# system_controller.net
KiCad netlist of a schematic drawn in Altium Designer
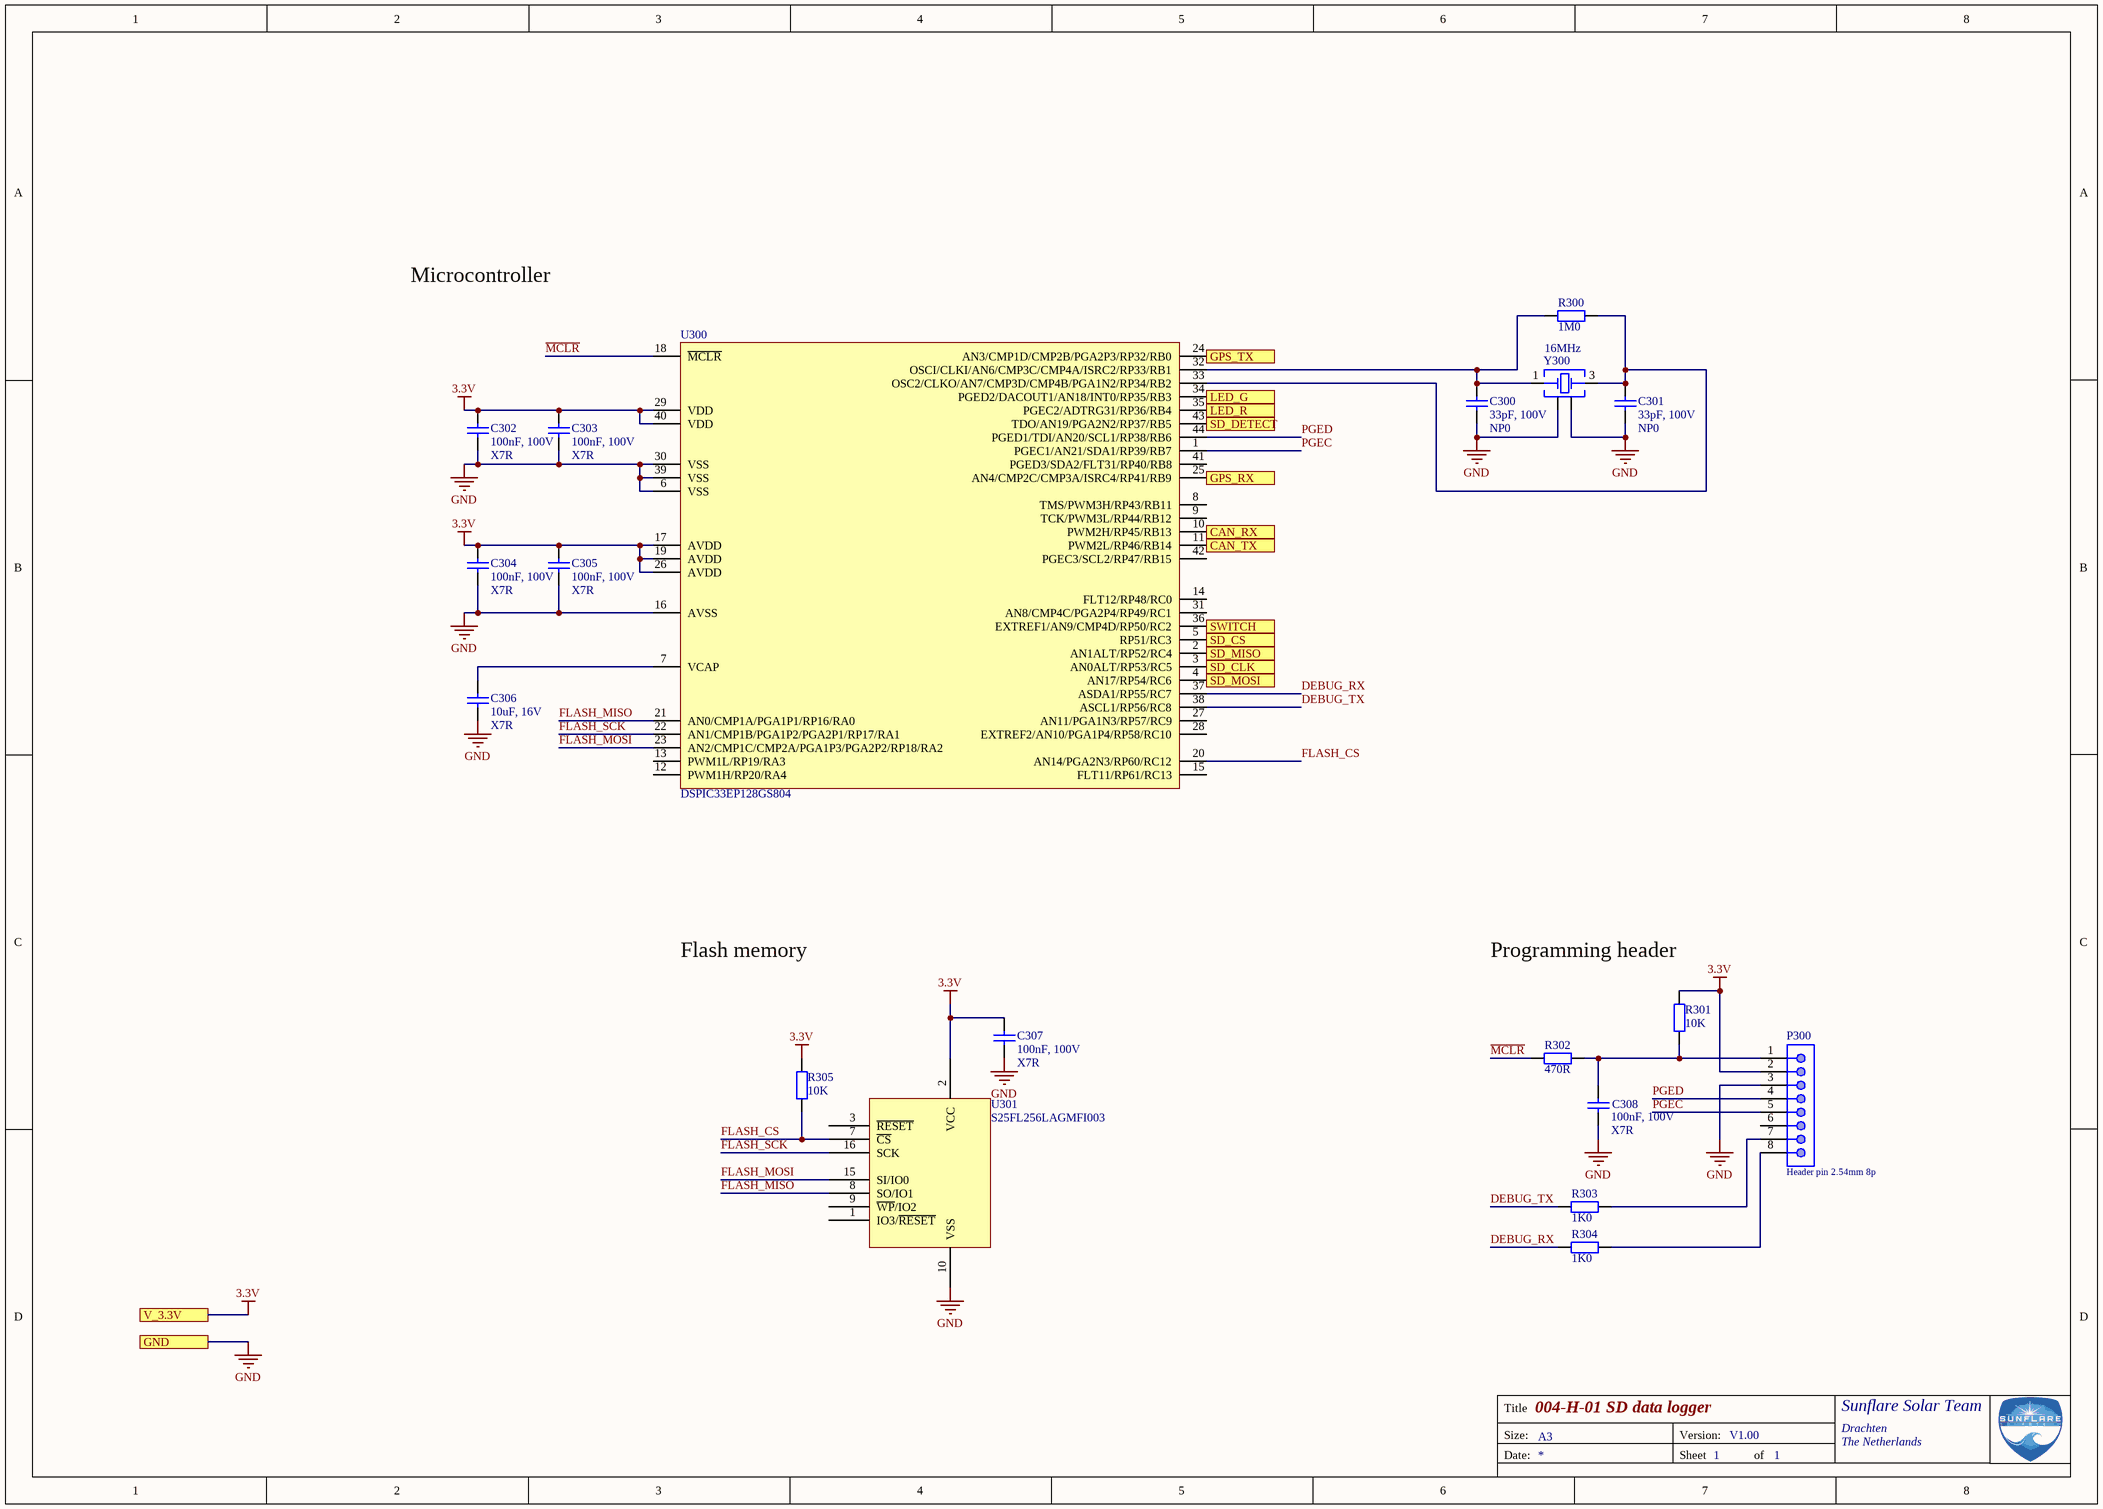
[diagram p0: system controller.SchDoc]

(export (version "E")
  (design (tool "Eeschema 10.0.6"))
  (components
    (comp (ref "C300")
      (value "33pF, 100V")
      (footprint "CAP_0805")
      (description "WCAP-CSGP Multilayer Ceramic Chip Capacitor, General Purpose, size 0805, NP0, 33pF, 100V")
      (fields
        (field (name "MANUFACTURER PART NUMBER") "885012007079")
        (field (name "MANUFACTURER") "Wurth Elektronik")
        (field (name "CERAMIC TYPE") "NP0")
      )
      (libsource (lib "004-H-01 SD data logger") (part "CAP_0805_33pF_100V"))
    )
    (comp (ref "C301")
      (value "33pF, 100V")
      (footprint "CAP_0805")
      (description "WCAP-CSGP Multilayer Ceramic Chip Capacitor, General Purpose, size 0805, NP0, 33pF, 100V")
      (fields
        (field (name "MANUFACTURER PART NUMBER") "885012007079")
        (field (name "MANUFACTURER") "Wurth Elektronik")
        (field (name "CERAMIC TYPE") "NP0")
      )
      (libsource (lib "004-H-01 SD data logger") (part "CAP_0805_33pF_100V"))
    )
    (comp (ref "C302")
      (value "100nF, 100V")
      (footprint "CAP_0805")
      (description "WCAP-CSGP Multilayer Ceramic Chip Capacitor, General Purpose, size 0805, X7R, 100nF, 100V")
      (fields
        (field (name "MANUFACTURER PART NUMBER") "885012207128")
        (field (name "MANUFACTURER") "Wurth Elektronik")
        (field (name "CERAMIC TYPE") "X7R")
      )
      (libsource (lib "004-H-01 SD data logger") (part "CAP_0805_100nF_100V"))
    )
    (comp (ref "C303")
      (value "100nF, 100V")
      (footprint "CAP_0805")
      (description "WCAP-CSGP Multilayer Ceramic Chip Capacitor, General Purpose, size 0805, X7R, 100nF, 100V")
      (fields
        (field (name "MANUFACTURER PART NUMBER") "885012207128")
        (field (name "MANUFACTURER") "Wurth Elektronik")
        (field (name "CERAMIC TYPE") "X7R")
      )
      (libsource (lib "004-H-01 SD data logger") (part "CAP_0805_100nF_100V"))
    )
    (comp (ref "C304")
      (value "100nF, 100V")
      (footprint "CAP_0805")
      (description "WCAP-CSGP Multilayer Ceramic Chip Capacitor, General Purpose, size 0805, X7R, 100nF, 100V")
      (fields
        (field (name "MANUFACTURER PART NUMBER") "885012207128")
        (field (name "MANUFACTURER") "Wurth Elektronik")
        (field (name "CERAMIC TYPE") "X7R")
      )
      (libsource (lib "004-H-01 SD data logger") (part "CAP_0805_100nF_100V"))
    )
    (comp (ref "C305")
      (value "100nF, 100V")
      (footprint "CAP_0805")
      (description "WCAP-CSGP Multilayer Ceramic Chip Capacitor, General Purpose, size 0805, X7R, 100nF, 100V")
      (fields
        (field (name "MANUFACTURER PART NUMBER") "885012207128")
        (field (name "MANUFACTURER") "Wurth Elektronik")
        (field (name "CERAMIC TYPE") "X7R")
      )
      (libsource (lib "004-H-01 SD data logger") (part "CAP_0805_100nF_100V"))
    )
    (comp (ref "C306")
      (value "10uF, 16V")
      (footprint "CAP_1210")
      (description "WCAP-CSGP Multilayer Ceramic Chip Capacitor, General Purpose, size 1210, X7R, 10uF, 16V")
      (fields
        (field (name "MANUFACTURER PART NUMBER") "885012209014")
        (field (name "MANUFACTURER") "Wurth Elektronik")
        (field (name "CERAMIC TYPE") "X7R")
      )
      (libsource (lib "004-H-01 SD data logger") (part "CAP_1210_10uF_16V"))
    )
    (comp (ref "C307")
      (value "100nF, 100V")
      (footprint "CAP_0805")
      (description "WCAP-CSGP Multilayer Ceramic Chip Capacitor, General Purpose, size 0805, X7R, 100nF, 100V")
      (fields
        (field (name "MANUFACTURER PART NUMBER") "885012207128")
        (field (name "MANUFACTURER") "Wurth Elektronik")
        (field (name "CERAMIC TYPE") "X7R")
      )
      (libsource (lib "004-H-01 SD data logger") (part "CAP_0805_100nF_100V"))
    )
    (comp (ref "C308")
      (value "100nF, 100V")
      (footprint "CAP_0805")
      (description "WCAP-CSGP Multilayer Ceramic Chip Capacitor, General Purpose, size 0805, X7R, 100nF, 100V")
      (fields
        (field (name "MANUFACTURER PART NUMBER") "885012207128")
        (field (name "MANUFACTURER") "Wurth Elektronik")
        (field (name "CERAMIC TYPE") "X7R")
      )
      (libsource (lib "004-H-01 SD data logger") (part "CAP_0805_100nF_100V"))
    )
    (comp (ref "P300")
      (value "Header pin 2.54mm 8p")
      (footprint "WE-61300811121")
      (description "WR-PHD Pin Header, THT, pitch 2.54mm, Single Row, Vertical, 8p")
      (fields
        (field (name "MANUFACTURER PART NUMBER") "61300811121")
        (field (name "MANUFACTURER") "Wurth Elektronik")
      )
      (libsource (lib "004-H-01 SD data logger") (part "Header pin 2.54mm 8p"))
    )
    (comp (ref "R300")
      (value "1M0")
      (footprint "RES_0805")
      (description "Thick Film Resistor, size 0805, 1%")
      (libsource (lib "004-H-01 SD data logger") (part "RES_0805_1M0"))
    )
    (comp (ref "R301")
      (value "10K")
      (footprint "RES_0805")
      (description "Thick Film Resistor, size 0805, 1%")
      (libsource (lib "004-H-01 SD data logger") (part "RES_0805_10K"))
    )
    (comp (ref "R302")
      (value "470R")
      (footprint "RES_0805")
      (description "Thick Film Resistor, size 0805, 1%")
      (libsource (lib "004-H-01 SD data logger") (part "RES_0805_470R"))
    )
    (comp (ref "R303")
      (value "1K0")
      (footprint "RES_0805")
      (description "Thick Film Resistor, size 0805, 1%")
      (libsource (lib "004-H-01 SD data logger") (part "RES_0805_1K0"))
    )
    (comp (ref "R304")
      (value "1K0")
      (footprint "RES_0805")
      (description "Thick Film Resistor, size 0805, 1%")
      (libsource (lib "004-H-01 SD data logger") (part "RES_0805_1K0"))
    )
    (comp (ref "R305")
      (value "10K")
      (footprint "RES_0805")
      (description "Thick Film Resistor, size 0805, 1%")
      (libsource (lib "004-H-01 SD data logger") (part "RES_0805_10K"))
    )
    (comp (ref "U300")
      (value "DSPIC33EP128GS804")
      (footprint "TQFP80P1200X1200X120-44N")
      (fields
        (field (name "MANUFACTURER") "Microchip")
        (field (name "MANUFACTURER PART NO") "DSPIC33EP128GS804-I/PT")
      )
      (libsource (lib "004-H-01 SD data logger") (part "DSPIC33EP128GS804"))
    )
    (comp (ref "U301")
      (value "S25FL256LAGMFI003")
      (footprint "SOIC127P1030X265-16N")
      (description "Flash Memory, Floating Gate Architecture, Serial NOR, 256 Mbit, 32M x 8bit, SPI, WSOIC, 16 Pins")
      (fields (field (name "MANUFACTURER") "Cypress - Infineon Technologies"))
      (libsource (lib "004-H-01 SD data logger") (part "S25FL256LAGMFI003"))
    )
    (comp (ref "Y300")
      (value "16MHz")
      (footprint "WE-XTAL_12SMX")
      (description "WE-XTAL Quartz Crystal, SMT, 12SMX, 16MHz, +/-30ppm")
      (fields
        (field (name "MANUFACTURER PART NUMBER") "830026392")
        (field (name "MANUFACTURER") "Wurth Elektronik")
      )
      (libsource (lib "004-H-01 SD data logger") (part "Crystal_16MHz"))
    )
  )
  (nets
    (net (code "1") (name "/CAN_RX") (class "Default")
      (node (ref "U300") (pin "10") (pinfunction "PWM2H/RP45/RB13_10") (pintype "passive"))
    )
    (net (code "2") (name "/CAN_TX") (class "Default")
      (node (ref "U300") (pin "11") (pinfunction "PWM2L/RP46/RB14_11") (pintype "passive"))
    )
    (net (code "3") (name "/DEBUG_RX") (class "Default")
      (node (ref "R304") (pin "1") (pinfunction "1_1") (pintype "passive"))
      (node (ref "U300") (pin "37") (pinfunction "ASDA1/RP55/RC7_37") (pintype "passive"))
    )
    (net (code "4") (name "/DEBUG_TX") (class "Default")
      (node (ref "R303") (pin "1") (pinfunction "1_1") (pintype "passive"))
      (node (ref "U300") (pin "38") (pinfunction "ASCL1/RP56/RC8_38") (pintype "passive"))
    )
    (net (code "5") (name "/FLASH_CS") (class "Default")
      (node (ref "R305") (pin "1") (pinfunction "1_1") (pintype "passive"))
      (node (ref "U300") (pin "20") (pinfunction "AN14/PGA2N3/RP60/RC12_20") (pintype "passive"))
      (node (ref "U301") (pin "7") (pinfunction "~{CS}_7") (pintype "passive"))
    )
    (net (code "6") (name "/FLASH_MISO") (class "Default")
      (node (ref "U300") (pin "21") (pinfunction "AN0/CMP1A/PGA1P1/RP16/RA0_21") (pintype "passive"))
      (node (ref "U301") (pin "8") (pinfunction "SO/IO1_8") (pintype "passive"))
    )
    (net (code "7") (name "/FLASH_MOSI") (class "Default")
      (node (ref "U300") (pin "23") (pinfunction "AN2/CMP1C/CMP2A/PGA1P3/PGA2P2/RP18/RA2_23") (pintype "passive"))
      (node (ref "U301") (pin "15") (pinfunction "SI/IO0_15") (pintype "passive"))
    )
    (net (code "8") (name "/FLASH_SCK") (class "Default")
      (node (ref "U300") (pin "22") (pinfunction "AN1/CMP1B/PGA1P2/PGA2P1/RP17/RA1_22") (pintype "passive"))
      (node (ref "U301") (pin "16") (pinfunction "SCK_16") (pintype "passive"))
    )
    (net (code "9") (name "/GPS_RX") (class "Default")
      (node (ref "U300") (pin "25") (pinfunction "AN4/CMP2C/CMP3A/ISRC4/RP41/RB9_25") (pintype "passive"))
    )
    (net (code "10") (name "/GPS_TX") (class "Default")
      (node (ref "U300") (pin "24") (pinfunction "AN3/CMP1D/CMP2B/PGA2P3/RP32/RB0_24") (pintype "passive"))
    )
    (net (code "11") (name "/LED_G") (class "Default")
      (node (ref "U300") (pin "34") (pinfunction "PGED2/DACOUT1/AN18/INT0/RP35/RB3_34") (pintype "passive"))
    )
    (net (code "12") (name "/LED_R") (class "Default")
      (node (ref "U300") (pin "35") (pinfunction "PGEC2/ADTRG31/RP36/RB4_35") (pintype "passive"))
    )
    (net (code "13") (name "/PGEC") (class "Default")
      (node (ref "P300") (pin "5") (pinfunction "5_5") (pintype "passive"))
      (node (ref "U300") (pin "1") (pinfunction "PGEC1/AN21/SDA1/RP39/RB7_1") (pintype "passive"))
    )
    (net (code "14") (name "/PGED") (class "Default")
      (node (ref "P300") (pin "4") (pinfunction "4_4") (pintype "passive"))
      (node (ref "U300") (pin "44") (pinfunction "PGED1/TDI/AN20/SCL1/RP38/RB6_44") (pintype "passive"))
    )
    (net (code "15") (name "/SD_CLK") (class "Default")
      (node (ref "U300") (pin "3") (pinfunction "AN0ALT/RP53/RC5_3") (pintype "passive"))
    )
    (net (code "16") (name "/SD_CS") (class "Default")
      (node (ref "U300") (pin "5") (pinfunction "RP51/RC3_5") (pintype "passive"))
    )
    (net (code "17") (name "/SD_DETECT") (class "Default")
      (node (ref "U300") (pin "43") (pinfunction "TDO/AN19/PGA2N2/RP37/RB5_43") (pintype "passive"))
    )
    (net (code "18") (name "/SD_MISO") (class "Default")
      (node (ref "U300") (pin "2") (pinfunction "AN1ALT/RP52/RC4_2") (pintype "passive"))
    )
    (net (code "19") (name "/SD_MOSI") (class "Default")
      (node (ref "U300") (pin "4") (pinfunction "AN17/RP54/RC6_4") (pintype "passive"))
    )
    (net (code "20") (name "/SWITCH") (class "Default")
      (node (ref "U300") (pin "36") (pinfunction "EXTREF1/AN9/CMP4D/RP50/RC2_36") (pintype "passive"))
    )
    (net (code "21") (name "/~{MCLR}") (class "Default")
      (node (ref "R302") (pin "1") (pinfunction "1_1") (pintype "passive"))
      (node (ref "U300") (pin "18") (pinfunction "~{MCLR}_18") (pintype "passive"))
    )
    (net (code "22") (name "3.3V") (class "Default")
      (node (ref "C302") (pin "2") (pinfunction "2_2") (pintype "passive"))
      (node (ref "C303") (pin "2") (pinfunction "2_2") (pintype "passive"))
      (node (ref "C304") (pin "2") (pinfunction "2_2") (pintype "passive"))
      (node (ref "C305") (pin "2") (pinfunction "2_2") (pintype "passive"))
      (node (ref "C307") (pin "2") (pinfunction "2_2") (pintype "passive"))
      (node (ref "P300") (pin "2") (pinfunction "2_2") (pintype "passive"))
      (node (ref "R301") (pin "2") (pinfunction "2_2") (pintype "passive"))
      (node (ref "R305") (pin "2") (pinfunction "2_2") (pintype "passive"))
      (node (ref "U300") (pin "17") (pinfunction "AVDD_17") (pintype "passive"))
      (node (ref "U300") (pin "19") (pinfunction "AVDD_19") (pintype "passive"))
      (node (ref "U300") (pin "26") (pinfunction "AVDD_26") (pintype "passive"))
      (node (ref "U300") (pin "29") (pinfunction "VDD_29") (pintype "passive"))
      (node (ref "U300") (pin "40") (pinfunction "VDD_40") (pintype "passive"))
      (node (ref "U301") (pin "2") (pinfunction "VCC_2") (pintype "passive"))
    )
    (net (code "23") (name "GND") (class "Default")
      (node (ref "C300") (pin "1") (pinfunction "1_1") (pintype "passive"))
      (node (ref "C301") (pin "1") (pinfunction "1_1") (pintype "passive"))
      (node (ref "C302") (pin "1") (pinfunction "1_1") (pintype "passive"))
      (node (ref "C303") (pin "1") (pinfunction "1_1") (pintype "passive"))
      (node (ref "C304") (pin "1") (pinfunction "1_1") (pintype "passive"))
      (node (ref "C305") (pin "1") (pinfunction "1_1") (pintype "passive"))
      (node (ref "C306") (pin "1") (pinfunction "1_1") (pintype "passive"))
      (node (ref "C307") (pin "1") (pinfunction "1_1") (pintype "passive"))
      (node (ref "C308") (pin "1") (pinfunction "1_1") (pintype "passive"))
      (node (ref "P300") (pin "3") (pinfunction "3_3") (pintype "passive"))
      (node (ref "U300") (pin "16") (pinfunction "AVSS_16") (pintype "passive"))
      (node (ref "U300") (pin "30") (pinfunction "VSS_30") (pintype "passive"))
      (node (ref "U300") (pin "39") (pinfunction "VSS_39") (pintype "passive"))
      (node (ref "U300") (pin "6") (pinfunction "VSS_6") (pintype "passive"))
      (node (ref "U301") (pin "10") (pinfunction "VSS_10") (pintype "passive"))
      (node (ref "Y300") (pin "2") (pinfunction "GND_&_Lid_2") (pintype "passive"))
      (node (ref "Y300") (pin "4") (pinfunction "GND_&_Lid_4") (pintype "passive"))
    )
    (net (code "24") (name "Net-(C308-Pad2)") (class "Default")
      (node (ref "C308") (pin "2") (pinfunction "2_2") (pintype "passive"))
      (node (ref "P300") (pin "1") (pinfunction "1_1") (pintype "passive"))
      (node (ref "R301") (pin "1") (pinfunction "1_1") (pintype "passive"))
      (node (ref "R302") (pin "2") (pinfunction "2_2") (pintype "passive"))
    )
    (net (code "25") (name "Net-(P300-Pad7)") (class "Default")
      (node (ref "P300") (pin "7") (pinfunction "7_7") (pintype "passive"))
      (node (ref "R303") (pin "2") (pinfunction "2_2") (pintype "passive"))
    )
    (net (code "26") (name "Net-(P300-Pad8)") (class "Default")
      (node (ref "P300") (pin "8") (pinfunction "8_8") (pintype "passive"))
      (node (ref "R304") (pin "2") (pinfunction "2_2") (pintype "passive"))
    )
    (net (code "27") (name "Net-(U300-OSC2{slash}CLKO{slash}AN7{slash}CMP3D{slash}CMP4B{slash}PGA1N2{slash}RP34{slash}RB2)") (class "Default")
      (node (ref "C301") (pin "2") (pinfunction "2_2") (pintype "passive"))
      (node (ref "R300") (pin "2") (pinfunction "2_2") (pintype "passive"))
      (node (ref "U300") (pin "33") (pinfunction "OSC2/CLKO/AN7/CMP3D/CMP4B/PGA1N2/RP34/RB2_33") (pintype "passive"))
      (node (ref "Y300") (pin "3") (pinfunction "Crystal_3") (pintype "passive"))
    )
    (net (code "28") (name "Net-(U300-OSCI{slash}CLKI{slash}AN6{slash}CMP3C{slash}CMP4A{slash}ISRC2{slash}RP33{slash}RB1)") (class "Default")
      (node (ref "C300") (pin "2") (pinfunction "2_2") (pintype "passive"))
      (node (ref "R300") (pin "1") (pinfunction "1_1") (pintype "passive"))
      (node (ref "U300") (pin "32") (pinfunction "OSCI/CLKI/AN6/CMP3C/CMP4A/ISRC2/RP33/RB1_32") (pintype "passive"))
      (node (ref "Y300") (pin "1") (pinfunction "Crystal_1") (pintype "passive"))
    )
    (net (code "29") (name "Net-(U300-VCAP)") (class "Default")
      (node (ref "C306") (pin "2") (pinfunction "2_2") (pintype "passive"))
      (node (ref "U300") (pin "7") (pinfunction "VCAP_7") (pintype "passive"))
    )
    (net (code "30") (name "unconnected-(P300-Pad6)") (class "Default")
      (node (ref "P300") (pin "6") (pinfunction "6_6") (pintype "passive"))
    )
    (net (code "31") (name "unconnected-(U300-AN8{slash}CMP4C{slash}PGA2P4{slash}RP49{slash}RC1-Pad31)") (class "Default")
      (node (ref "U300") (pin "31") (pinfunction "AN8/CMP4C/PGA2P4/RP49/RC1_31") (pintype "passive"))
    )
    (net (code "32") (name "unconnected-(U300-AN11{slash}PGA1N3{slash}RP57{slash}RC9-Pad27)") (class "Default")
      (node (ref "U300") (pin "27") (pinfunction "AN11/PGA1N3/RP57/RC9_27") (pintype "passive"))
    )
    (net (code "33") (name "unconnected-(U300-EXTREF2{slash}AN10{slash}PGA1P4{slash}RP58{slash}RC10-Pad28)") (class "Default")
      (node (ref "U300") (pin "28") (pinfunction "EXTREF2/AN10/PGA1P4/RP58/RC10_28") (pintype "passive"))
    )
    (net (code "34") (name "unconnected-(U300-FLT11{slash}RP61{slash}RC13-Pad15)") (class "Default")
      (node (ref "U300") (pin "15") (pinfunction "FLT11/RP61/RC13_15") (pintype "passive"))
    )
    (net (code "35") (name "unconnected-(U300-FLT12{slash}RP48{slash}RC0-Pad14)") (class "Default")
      (node (ref "U300") (pin "14") (pinfunction "FLT12/RP48/RC0_14") (pintype "passive"))
    )
    (net (code "36") (name "unconnected-(U300-PGEC3{slash}SCL2{slash}RP47{slash}RB15-Pad42)") (class "Default")
      (node (ref "U300") (pin "42") (pinfunction "PGEC3/SCL2/RP47/RB15_42") (pintype "passive"))
    )
    (net (code "37") (name "unconnected-(U300-PGED3{slash}SDA2{slash}FLT31{slash}RP40{slash}RB8-Pad41)") (class "Default")
      (node (ref "U300") (pin "41") (pinfunction "PGED3/SDA2/FLT31/RP40/RB8_41") (pintype "passive"))
    )
    (net (code "38") (name "unconnected-(U300-PWM1H{slash}RP20{slash}RA4-Pad12)") (class "Default")
      (node (ref "U300") (pin "12") (pinfunction "PWM1H/RP20/RA4_12") (pintype "passive"))
    )
    (net (code "39") (name "unconnected-(U300-PWM1L{slash}RP19{slash}RA3-Pad13)") (class "Default")
      (node (ref "U300") (pin "13") (pinfunction "PWM1L/RP19/RA3_13") (pintype "passive"))
    )
    (net (code "40") (name "unconnected-(U300-TCK{slash}PWM3L{slash}RP44{slash}RB12-Pad9)") (class "Default")
      (node (ref "U300") (pin "9") (pinfunction "TCK/PWM3L/RP44/RB12_9") (pintype "passive"))
    )
    (net (code "41") (name "unconnected-(U300-TMS{slash}PWM3H{slash}RP43{slash}RB11-Pad8)") (class "Default")
      (node (ref "U300") (pin "8") (pinfunction "TMS/PWM3H/RP43/RB11_8") (pintype "passive"))
    )
    (net (code "42") (name "unconnected-(U301-IO3{slash}~{RESET}-Pad1)") (class "Default")
      (node (ref "U301") (pin "1") (pinfunction "IO3/~{RESET}_1") (pintype "passive"))
    )
    (net (code "43") (name "unconnected-(U301-~{RESET}-Pad3)") (class "Default")
      (node (ref "U301") (pin "3") (pinfunction "~{RESET}_3") (pintype "passive"))
    )
    (net (code "44") (name "unconnected-(U301-~{WP}{slash}IO2-Pad9)") (class "Default")
      (node (ref "U301") (pin "9") (pinfunction "~{WP}/IO2_9") (pintype "passive"))
    )
  )
)
